# Sensors.net
KiCad netlist of a schematic drawn in Altium Designer
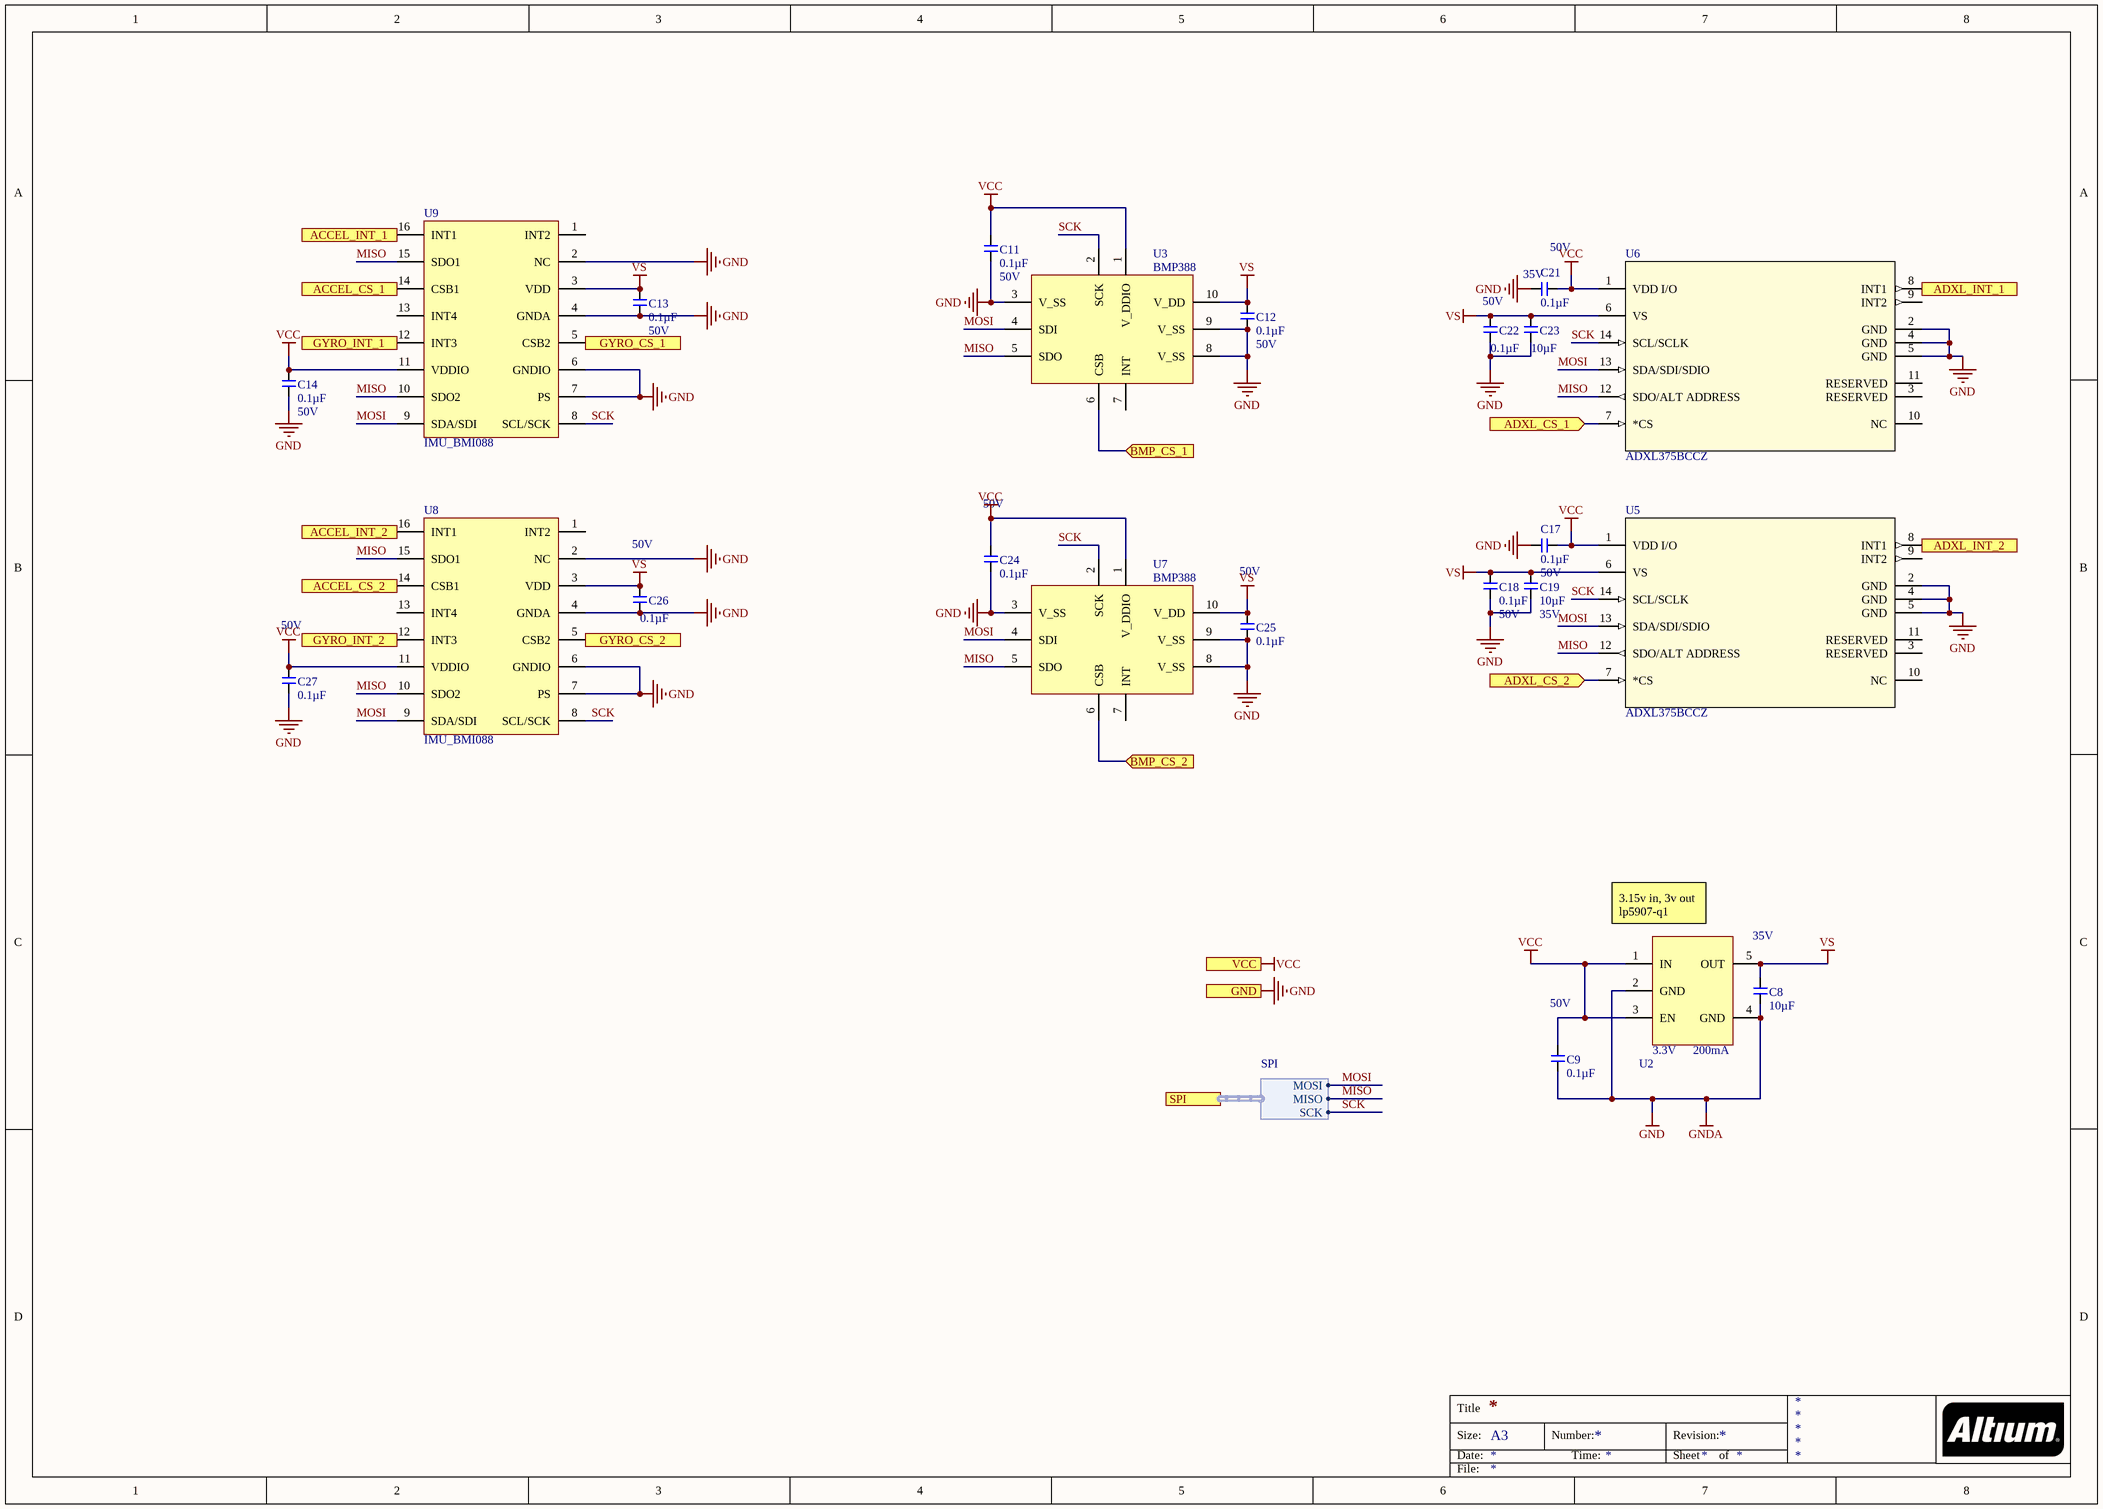
[diagram p0: Sensors.SchDoc]

(export (version "E")
  (design (tool "Eeschema 10.0.6"))
  (components
    (comp (ref "C8")
      (value "490-13248-1-ND")
      (footprint "C0603")
      (description "CAP CER 10UF 35V X5R 0603 20%")
      (fields
        (field (name "CAPACITANCE (SHORTHAND)") "10µF")
        (field (name "MANUFACTURER") "Murata Electronics North America")
        (field (name "RATED VOLTAGE") "35V")
      )
      (libsource (lib "Stanford Student Space Initiative") (part "__template_cap"))
    )
    (comp (ref "C9")
      (value "490-1519-1-ND")
      (footprint "C0603")
      (description "CAP CER 0603 0.1µF X7R 50V 10%")
      (fields
        (field (name "CAPACITANCE (SHORTHAND)") "0.1µF")
        (field (name "MANUFACTURER") "Murata Electronics North America")
        (field (name "RATED VOLTAGE") "50V")
      )
      (libsource (lib "Stanford Student Space Initiative") (part "__template_cap"))
    )
    (comp (ref "C11")
      (value "490-1519-1-ND")
      (footprint "C0603")
      (description "CAP CER 0603 0.1µF X7R 50V 10%")
      (fields
        (field (name "CAPACITANCE (SHORTHAND)") "0.1µF")
        (field (name "MANUFACTURER") "Murata Electronics North America")
        (field (name "RATED VOLTAGE") "50V")
      )
      (libsource (lib "Stanford Student Space Initiative") (part "__template_cap"))
    )
    (comp (ref "C12")
      (value "490-1519-1-ND")
      (footprint "C0603")
      (description "CAP CER 0603 0.1µF X7R 50V 10%")
      (fields
        (field (name "CAPACITANCE (SHORTHAND)") "0.1µF")
        (field (name "MANUFACTURER") "Murata Electronics North America")
        (field (name "RATED VOLTAGE") "50V")
      )
      (libsource (lib "Stanford Student Space Initiative") (part "__template_cap"))
    )
    (comp (ref "C13")
      (value "490-1519-1-ND")
      (footprint "C0603")
      (description "CAP CER 0603 0.1µF X7R 50V 10%")
      (fields
        (field (name "CAPACITANCE (SHORTHAND)") "0.1µF")
        (field (name "MANUFACTURER") "Murata Electronics North America")
        (field (name "RATED VOLTAGE") "50V")
      )
      (libsource (lib "Stanford Student Space Initiative") (part "__template_cap"))
    )
    (comp (ref "C14")
      (value "490-1519-1-ND")
      (footprint "C0603")
      (description "CAP CER 0603 0.1µF X7R 50V 10%")
      (fields
        (field (name "CAPACITANCE (SHORTHAND)") "0.1µF")
        (field (name "MANUFACTURER") "Murata Electronics North America")
        (field (name "RATED VOLTAGE") "50V")
      )
      (libsource (lib "Stanford Student Space Initiative") (part "__template_cap"))
    )
    (comp (ref "C17")
      (value "490-1519-1-ND")
      (footprint "C0603")
      (description "CAP CER 0603 0.1µF X7R 50V 10%")
      (fields
        (field (name "CAPACITANCE (SHORTHAND)") "0.1µF")
        (field (name "MANUFACTURER") "Murata Electronics North America")
        (field (name "RATED VOLTAGE") "50V")
      )
      (libsource (lib "Stanford Student Space Initiative") (part "__template_cap"))
    )
    (comp (ref "C18")
      (value "490-1519-1-ND")
      (footprint "C0603")
      (description "CAP CER 0603 0.1µF X7R 50V 10%")
      (fields
        (field (name "CAPACITANCE (SHORTHAND)") "0.1µF")
        (field (name "MANUFACTURER") "Murata Electronics North America")
        (field (name "RATED VOLTAGE") "50V")
      )
      (libsource (lib "Stanford Student Space Initiative") (part "__template_cap"))
    )
    (comp (ref "C19")
      (value "490-13248-1-ND")
      (footprint "C0603")
      (description "CAP CER 10UF 35V X5R 0603 20%")
      (fields
        (field (name "CAPACITANCE (SHORTHAND)") "10µF")
        (field (name "MANUFACTURER") "Murata Electronics North America")
        (field (name "RATED VOLTAGE") "35V")
      )
      (libsource (lib "Stanford Student Space Initiative") (part "__template_cap"))
    )
    (comp (ref "C21")
      (value "490-1519-1-ND")
      (footprint "C0603")
      (description "CAP CER 0603 0.1µF X7R 50V 10%")
      (fields
        (field (name "CAPACITANCE (SHORTHAND)") "0.1µF")
        (field (name "MANUFACTURER") "Murata Electronics North America")
        (field (name "RATED VOLTAGE") "50V")
      )
      (libsource (lib "Stanford Student Space Initiative") (part "__template_cap"))
    )
    (comp (ref "C22")
      (value "490-1519-1-ND")
      (footprint "C0603")
      (description "CAP CER 0603 0.1µF X7R 50V 10%")
      (fields
        (field (name "CAPACITANCE (SHORTHAND)") "0.1µF")
        (field (name "MANUFACTURER") "Murata Electronics North America")
        (field (name "RATED VOLTAGE") "50V")
      )
      (libsource (lib "Stanford Student Space Initiative") (part "__template_cap"))
    )
    (comp (ref "C23")
      (value "490-13248-1-ND")
      (footprint "C0603")
      (description "CAP CER 10UF 35V X5R 0603 20%")
      (fields
        (field (name "CAPACITANCE (SHORTHAND)") "10µF")
        (field (name "MANUFACTURER") "Murata Electronics North America")
        (field (name "RATED VOLTAGE") "35V")
      )
      (libsource (lib "Stanford Student Space Initiative") (part "__template_cap"))
    )
    (comp (ref "C24")
      (value "490-1519-1-ND")
      (footprint "C0603")
      (description "CAP CER 0603 0.1µF X7R 50V 10%")
      (fields
        (field (name "CAPACITANCE (SHORTHAND)") "0.1µF")
        (field (name "MANUFACTURER") "Murata Electronics North America")
        (field (name "RATED VOLTAGE") "50V")
      )
      (libsource (lib "Stanford Student Space Initiative") (part "__template_cap"))
    )
    (comp (ref "C25")
      (value "490-1519-1-ND")
      (footprint "C0603")
      (description "CAP CER 0603 0.1µF X7R 50V 10%")
      (fields
        (field (name "CAPACITANCE (SHORTHAND)") "0.1µF")
        (field (name "MANUFACTURER") "Murata Electronics North America")
        (field (name "RATED VOLTAGE") "50V")
      )
      (libsource (lib "Stanford Student Space Initiative") (part "__template_cap"))
    )
    (comp (ref "C26")
      (value "490-1519-1-ND")
      (footprint "C0603")
      (description "CAP CER 0603 0.1µF X7R 50V 10%")
      (fields
        (field (name "CAPACITANCE (SHORTHAND)") "0.1µF")
        (field (name "MANUFACTURER") "Murata Electronics North America")
        (field (name "RATED VOLTAGE") "50V")
      )
      (libsource (lib "Stanford Student Space Initiative") (part "__template_cap"))
    )
    (comp (ref "C27")
      (value "490-1519-1-ND")
      (footprint "C0603")
      (description "CAP CER 0603 0.1µF X7R 50V 10%")
      (fields
        (field (name "CAPACITANCE (SHORTHAND)") "0.1µF")
        (field (name "MANUFACTURER") "Murata Electronics North America")
        (field (name "RATED VOLTAGE") "50V")
      )
      (libsource (lib "Stanford Student Space Initiative") (part "__template_cap"))
    )
    (comp (ref "U2")
      (value "LDO_TLV70033QDDCRQ1")
      (footprint "5SOT23")
      (description "IC REG LDO 3.3V .2A SOT23-5")
      (fields
        (field (name "MANUFACTURER") "Texas Instruments")
        (field (name "MANUFACTURER PART NUMBER") "TLV70033QDDCRQ1")
        (field (name "VOLTAGE - OUTPUT") "3.3V")
        (field (name "CURRENT - OUTPUT") "200mA")
      )
      (libsource (lib "Stanford Student Space Initiative") (part "LDO_TLV70033QDDCRQ1"))
    )
    (comp (ref "U3")
      (value "BMP388")
      (footprint "8 pin LGA")
      (description "SENSOR PRESSURE ABS")
      (fields (field (name "MANUFACTURER") "Bosch Sensortec"))
      (libsource (lib "Stanford Student Space Initiative") (part "BMP388"))
    )
    (comp (ref "U5")
      (value "ADXL375BCCZ")
      (footprint "LGA_CC-14-1")
      (description "200G Accelcerometer")
      (fields
        (field (name "MANUFACTURER") "Analog Devices")
        (field (name "MANUFACTURER PART NUMBER") "ADXL375BCCZ-RL7")
      )
      (libsource (lib "Stanford Student Space Initiative") (part "ADXL375BCCZ"))
    )
    (comp (ref "U6")
      (value "ADXL375BCCZ")
      (footprint "LGA_CC-14-1")
      (description "200G Accelcerometer")
      (fields
        (field (name "MANUFACTURER") "Analog Devices")
        (field (name "MANUFACTURER PART NUMBER") "ADXL375BCCZ-RL7")
      )
      (libsource (lib "Stanford Student Space Initiative") (part "ADXL375BCCZ"))
    )
    (comp (ref "U7")
      (value "BMP388")
      (footprint "8 pin LGA")
      (description "SENSOR PRESSURE ABS")
      (fields (field (name "MANUFACTURER") "Bosch Sensortec"))
      (libsource (lib "Stanford Student Space Initiative") (part "BMP388"))
    )
    (comp (ref "U8")
      (value "IMU_BMI088")
      (footprint "BMI088")
      (description "Bosch BMI088")
      (libsource (lib "Stanford Student Space Initiative") (part "IMU_BMI088"))
    )
    (comp (ref "U9")
      (value "IMU_BMI088")
      (footprint "BMI088")
      (description "Bosch BMI088")
      (libsource (lib "Stanford Student Space Initiative") (part "IMU_BMI088"))
    )
  )
  (nets
    (net (code "2") (name "/ACCEL_CS_1") (class "Default")
      (node (ref "U9") (pin "14") (pinfunction "CSB1_14") (pintype "passive"))
    )
    (net (code "3") (name "/ACCEL_CS_2") (class "Default")
      (node (ref "U8") (pin "14") (pinfunction "CSB1_14") (pintype "passive"))
    )
    (net (code "4") (name "/ACCEL_INT_1") (class "Default")
      (node (ref "U9") (pin "16") (pinfunction "INT1_16") (pintype "passive"))
    )
    (net (code "5") (name "/ACCEL_INT_2") (class "Default")
      (node (ref "U8") (pin "16") (pinfunction "INT1_16") (pintype "passive"))
    )
    (net (code "6") (name "/ADXL_CS_1") (class "Default")
      (node (ref "U6") (pin "7") (pinfunction "*CS_7") (pintype "input"))
    )
    (net (code "7") (name "/ADXL_CS_2") (class "Default")
      (node (ref "U5") (pin "7") (pinfunction "*CS_7") (pintype "input"))
    )
    (net (code "8") (name "/ADXL_INT_1") (class "Default")
      (node (ref "U6") (pin "8") (pinfunction "INT1_8") (pintype "output"))
    )
    (net (code "9") (name "/ADXL_INT_2") (class "Default")
      (node (ref "U5") (pin "8") (pinfunction "INT1_8") (pintype "output"))
    )
    (net (code "10") (name "/BMP_CS_1") (class "Default")
      (node (ref "U3") (pin "6") (pinfunction "CSB_6") (pintype "passive"))
    )
    (net (code "11") (name "/BMP_CS_2") (class "Default")
      (node (ref "U7") (pin "6") (pinfunction "CSB_6") (pintype "passive"))
    )
    (net (code "12") (name "/GYRO_CS_1") (class "Default")
      (node (ref "U9") (pin "5") (pinfunction "CSB2_5") (pintype "passive"))
    )
    (net (code "13") (name "/GYRO_CS_2") (class "Default")
      (node (ref "U8") (pin "5") (pinfunction "CSB2_5") (pintype "passive"))
    )
    (net (code "14") (name "/GYRO_INT_1") (class "Default")
      (node (ref "U9") (pin "12") (pinfunction "INT3_12") (pintype "passive"))
    )
    (net (code "15") (name "/GYRO_INT_2") (class "Default")
      (node (ref "U8") (pin "12") (pinfunction "INT3_12") (pintype "passive"))
    )
    (net (code "16") (name "/MISO") (class "Default")
      (node (ref "U3") (pin "5") (pinfunction "SDO_5") (pintype "passive"))
      (node (ref "U5") (pin "12") (pinfunction "SDO/ALT_ADDRESS_12") (pintype "output"))
      (node (ref "U6") (pin "12") (pinfunction "SDO/ALT_ADDRESS_12") (pintype "output"))
      (node (ref "U7") (pin "5") (pinfunction "SDO_5") (pintype "passive"))
      (node (ref "U8") (pin "10") (pinfunction "SDO2_10") (pintype "passive"))
      (node (ref "U8") (pin "15") (pinfunction "SDO1_15") (pintype "passive"))
      (node (ref "U9") (pin "10") (pinfunction "SDO2_10") (pintype "passive"))
      (node (ref "U9") (pin "15") (pinfunction "SDO1_15") (pintype "passive"))
    )
    (net (code "17") (name "/MOSI") (class "Default")
      (node (ref "U3") (pin "4") (pinfunction "SDI_4") (pintype "passive"))
      (node (ref "U5") (pin "13") (pinfunction "SDA/SDI/SDIO_13") (pintype "input"))
      (node (ref "U6") (pin "13") (pinfunction "SDA/SDI/SDIO_13") (pintype "input"))
      (node (ref "U7") (pin "4") (pinfunction "SDI_4") (pintype "passive"))
      (node (ref "U8") (pin "9") (pinfunction "SDA/SDI_9") (pintype "passive"))
      (node (ref "U9") (pin "9") (pinfunction "SDA/SDI_9") (pintype "passive"))
    )
    (net (code "18") (name "/SCK") (class "Default")
      (node (ref "U3") (pin "2") (pinfunction "SCK_2") (pintype "passive"))
      (node (ref "U5") (pin "14") (pinfunction "SCL/SCLK_14") (pintype "input"))
      (node (ref "U6") (pin "14") (pinfunction "SCL/SCLK_14") (pintype "input"))
      (node (ref "U7") (pin "2") (pinfunction "SCK_2") (pintype "passive"))
      (node (ref "U8") (pin "8") (pinfunction "SCL/SCK_8") (pintype "passive"))
      (node (ref "U9") (pin "8") (pinfunction "SCL/SCK_8") (pintype "passive"))
    )
    (net (code "20") (name "GND") (class "Default")
      (node (ref "C11") (pin "2") (pintype "passive"))
      (node (ref "C12") (pin "2") (pintype "passive"))
      (node (ref "C13") (pin "2") (pintype "passive"))
      (node (ref "C14") (pin "2") (pintype "passive"))
      (node (ref "C17") (pin "2") (pintype "passive"))
      (node (ref "C18") (pin "1") (pintype "passive"))
      (node (ref "C19") (pin "2") (pintype "passive"))
      (node (ref "C21") (pin "2") (pintype "passive"))
      (node (ref "C22") (pin "1") (pintype "passive"))
      (node (ref "C23") (pin "2") (pintype "passive"))
      (node (ref "C24") (pin "2") (pintype "passive"))
      (node (ref "C25") (pin "2") (pintype "passive"))
      (node (ref "C26") (pin "2") (pintype "passive"))
      (node (ref "C27") (pin "2") (pintype "passive"))
      (node (ref "C8") (pin "2") (pintype "passive"))
      (node (ref "C9") (pin "2") (pintype "passive"))
      (node (ref "U2") (pin "2") (pinfunction "GND_2") (pintype "passive"))
      (node (ref "U2") (pin "4") (pinfunction "GND_4") (pintype "passive"))
      (node (ref "U3") (pin "3") (pinfunction "V_SS_3") (pintype "passive"))
      (node (ref "U3") (pin "8") (pinfunction "V_SS_8") (pintype "passive"))
      (node (ref "U3") (pin "9") (pinfunction "V_SS_9") (pintype "passive"))
      (node (ref "U5") (pin "2") (pinfunction "GND_2") (pintype "power_in"))
      (node (ref "U5") (pin "4") (pinfunction "GND_4") (pintype "power_in"))
      (node (ref "U5") (pin "5") (pinfunction "GND_5") (pintype "power_in"))
      (node (ref "U6") (pin "2") (pinfunction "GND_2") (pintype "power_in"))
      (node (ref "U6") (pin "4") (pinfunction "GND_4") (pintype "power_in"))
      (node (ref "U6") (pin "5") (pinfunction "GND_5") (pintype "power_in"))
      (node (ref "U7") (pin "3") (pinfunction "V_SS_3") (pintype "passive"))
      (node (ref "U7") (pin "8") (pinfunction "V_SS_8") (pintype "passive"))
      (node (ref "U7") (pin "9") (pinfunction "V_SS_9") (pintype "passive"))
      (node (ref "U8") (pin "2") (pinfunction "NC_2") (pintype "passive"))
      (node (ref "U8") (pin "4") (pinfunction "GNDA_4") (pintype "passive"))
      (node (ref "U8") (pin "6") (pinfunction "GNDIO_6") (pintype "passive"))
      (node (ref "U8") (pin "7") (pinfunction "PS_7") (pintype "passive"))
      (node (ref "U9") (pin "2") (pinfunction "NC_2") (pintype "passive"))
      (node (ref "U9") (pin "4") (pinfunction "GNDA_4") (pintype "passive"))
      (node (ref "U9") (pin "6") (pinfunction "GNDIO_6") (pintype "passive"))
      (node (ref "U9") (pin "7") (pinfunction "PS_7") (pintype "passive"))
    )
    (net (code "21") (name "VCC") (class "Default")
      (node (ref "C11") (pin "1") (pintype "passive"))
      (node (ref "C14") (pin "1") (pintype "passive"))
      (node (ref "C17") (pin "1") (pintype "passive"))
      (node (ref "C21") (pin "1") (pintype "passive"))
      (node (ref "C24") (pin "1") (pintype "passive"))
      (node (ref "C27") (pin "1") (pintype "passive"))
      (node (ref "C9") (pin "1") (pintype "passive"))
      (node (ref "U2") (pin "1") (pinfunction "IN_1") (pintype "passive"))
      (node (ref "U2") (pin "3") (pinfunction "EN_3") (pintype "passive"))
      (node (ref "U3") (pin "1") (pinfunction "V_DDIO_1") (pintype "passive"))
      (node (ref "U5") (pin "1") (pinfunction "VDD_I/O_1") (pintype "power_in"))
      (node (ref "U6") (pin "1") (pinfunction "VDD_I/O_1") (pintype "power_in"))
      (node (ref "U7") (pin "1") (pinfunction "V_DDIO_1") (pintype "passive"))
      (node (ref "U8") (pin "11") (pinfunction "VDDIO_11") (pintype "passive"))
      (node (ref "U9") (pin "11") (pinfunction "VDDIO_11") (pintype "passive"))
    )
    (net (code "22") (name "VS") (class "Default")
      (node (ref "C12") (pin "1") (pintype "passive"))
      (node (ref "C13") (pin "1") (pintype "passive"))
      (node (ref "C18") (pin "2") (pintype "passive"))
      (node (ref "C19") (pin "1") (pintype "passive"))
      (node (ref "C22") (pin "2") (pintype "passive"))
      (node (ref "C23") (pin "1") (pintype "passive"))
      (node (ref "C25") (pin "1") (pintype "passive"))
      (node (ref "C26") (pin "1") (pintype "passive"))
      (node (ref "C8") (pin "1") (pintype "passive"))
      (node (ref "U2") (pin "5") (pinfunction "OUT_5") (pintype "passive"))
      (node (ref "U3") (pin "10") (pinfunction "V_DD_10") (pintype "passive"))
      (node (ref "U5") (pin "6") (pinfunction "VS_6") (pintype "power_in"))
      (node (ref "U6") (pin "6") (pinfunction "VS_6") (pintype "power_in"))
      (node (ref "U7") (pin "10") (pinfunction "V_DD_10") (pintype "passive"))
      (node (ref "U8") (pin "3") (pinfunction "VDD_3") (pintype "passive"))
      (node (ref "U9") (pin "3") (pinfunction "VDD_3") (pintype "passive"))
    )
    (net (code "23") (name "unconnected-(U3-INT-Pad7)") (class "Default")
      (node (ref "U3") (pin "7") (pinfunction "INT_7") (pintype "passive"))
    )
    (net (code "24") (name "unconnected-(U5-INT2-Pad9)") (class "Default")
      (node (ref "U5") (pin "9") (pinfunction "INT2_9") (pintype "output"))
    )
    (net (code "25") (name "unconnected-(U5-NC-Pad10)") (class "Default")
      (node (ref "U5") (pin "10") (pinfunction "NC_10") (pintype "passive"))
    )
    (net (code "26") (name "unconnected-(U5-RESERVED-Pad3)") (class "Default")
      (node (ref "U5") (pin "3") (pinfunction "RESERVED_3") (pintype "passive"))
    )
    (net (code "27") (name "unconnected-(U5-RESERVED-Pad11)") (class "Default")
      (node (ref "U5") (pin "11") (pinfunction "RESERVED_11") (pintype "passive"))
    )
    (net (code "28") (name "unconnected-(U6-INT2-Pad9)") (class "Default")
      (node (ref "U6") (pin "9") (pinfunction "INT2_9") (pintype "output"))
    )
    (net (code "29") (name "unconnected-(U6-NC-Pad10)") (class "Default")
      (node (ref "U6") (pin "10") (pinfunction "NC_10") (pintype "passive"))
    )
    (net (code "30") (name "unconnected-(U6-RESERVED-Pad3)") (class "Default")
      (node (ref "U6") (pin "3") (pinfunction "RESERVED_3") (pintype "passive"))
    )
    (net (code "31") (name "unconnected-(U6-RESERVED-Pad11)") (class "Default")
      (node (ref "U6") (pin "11") (pinfunction "RESERVED_11") (pintype "passive"))
    )
    (net (code "32") (name "unconnected-(U7-INT-Pad7)") (class "Default")
      (node (ref "U7") (pin "7") (pinfunction "INT_7") (pintype "passive"))
    )
    (net (code "33") (name "unconnected-(U8-INT2-Pad1)") (class "Default")
      (node (ref "U8") (pin "1") (pinfunction "INT2_1") (pintype "passive"))
    )
    (net (code "34") (name "unconnected-(U8-INT4-Pad13)") (class "Default")
      (node (ref "U8") (pin "13") (pinfunction "INT4_13") (pintype "passive"))
    )
    (net (code "35") (name "unconnected-(U9-INT2-Pad1)") (class "Default")
      (node (ref "U9") (pin "1") (pinfunction "INT2_1") (pintype "passive"))
    )
    (net (code "36") (name "unconnected-(U9-INT4-Pad13)") (class "Default")
      (node (ref "U9") (pin "13") (pinfunction "INT4_13") (pintype "passive"))
    )
  )
)
